# Main.net
KiCad netlist of a schematic drawn in Altium Designer
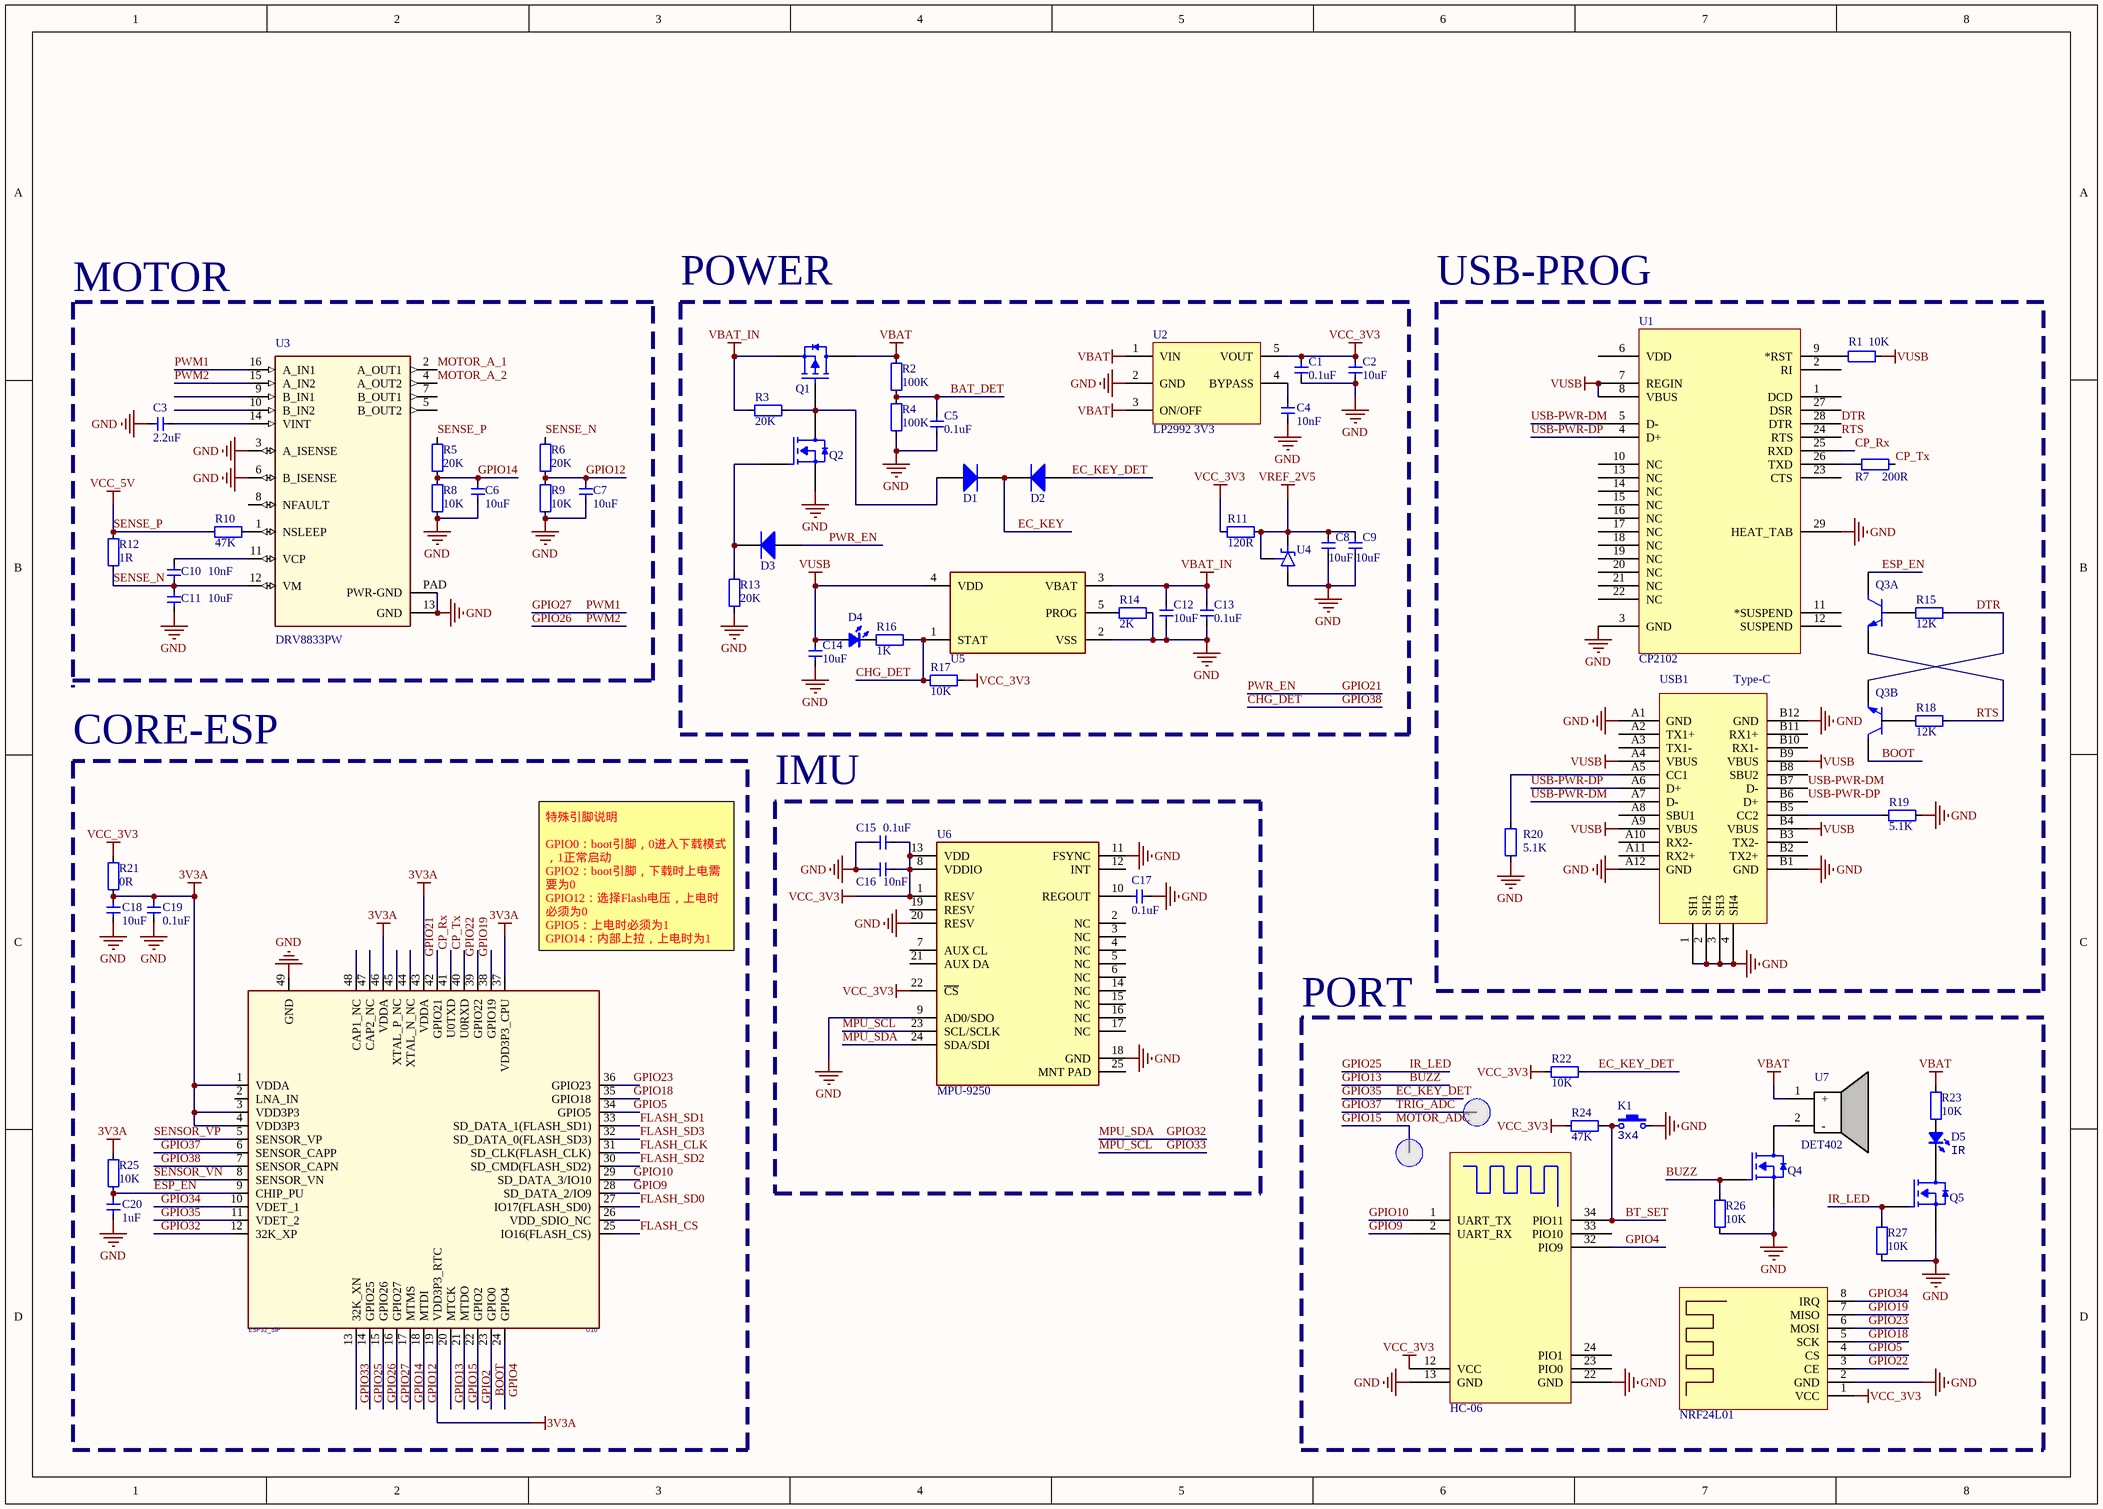
[diagram p0: Main.SchDoc]

(export (version "E")
  (design (tool "Eeschema 10.0.6"))
  (components
    (comp (ref "C1")
      (value "0.1uF")
      (footprint "CAP_0402")
      (description "Capacitor")
      (libsource (lib "MyPcbLib") (part "电容-0402"))
    )
    (comp (ref "C2")
      (value "10uF")
      (footprint "CAP_0402")
      (description "Capacitor")
      (libsource (lib "MyPcbLib") (part "电容-0402"))
    )
    (comp (ref "C3")
      (value "2.2uF")
      (footprint "CAP_0402")
      (description "Capacitor")
      (libsource (lib "MyPcbLib") (part "电容-0402"))
    )
    (comp (ref "C4")
      (value "10nF")
      (footprint "CAP_0402")
      (description "Capacitor")
      (libsource (lib "MyPcbLib") (part "电容-0402"))
    )
    (comp (ref "C5")
      (value "0.1uF")
      (footprint "CAP_0402")
      (description "Capacitor")
      (libsource (lib "MyPcbLib") (part "电容-0402"))
    )
    (comp (ref "C6")
      (value "10uF")
      (footprint "CAP_0402")
      (description "Capacitor")
      (libsource (lib "MyPcbLib") (part "电容-0402"))
    )
    (comp (ref "C7")
      (value "10uF")
      (footprint "CAP_0402")
      (description "Capacitor")
      (libsource (lib "MyPcbLib") (part "电容-0402"))
    )
    (comp (ref "C8")
      (value "10uF")
      (footprint "CAP_0402")
      (description "Capacitor")
      (libsource (lib "MyPcbLib") (part "电容-0402"))
    )
    (comp (ref "C9")
      (value "10uF")
      (footprint "CAP_0402")
      (description "Capacitor")
      (libsource (lib "MyPcbLib") (part "电容-0402"))
    )
    (comp (ref "C10")
      (value "10nF")
      (footprint "CAP_0402")
      (description "Capacitor")
      (libsource (lib "MyPcbLib") (part "电容-0402"))
    )
    (comp (ref "C11")
      (value "10uF")
      (footprint "CAP_0402")
      (description "Capacitor")
      (libsource (lib "MyPcbLib") (part "电容-0402"))
    )
    (comp (ref "C12")
      (value "10uF")
      (footprint "CAP_0402")
      (description "Capacitor")
      (libsource (lib "MyPcbLib") (part "电容-0402"))
    )
    (comp (ref "C13")
      (value "0.1uF")
      (footprint "CAP_0402")
      (description "Capacitor")
      (libsource (lib "MyPcbLib") (part "电容-0402"))
    )
    (comp (ref "C14")
      (value "10uF")
      (footprint "CAP_0402")
      (description "Capacitor")
      (libsource (lib "MyPcbLib") (part "电容-0402"))
    )
    (comp (ref "C15")
      (value "0.1uF")
      (footprint "CAP_0402")
      (description "Capacitor")
      (libsource (lib "MyPcbLib") (part "电容-0402"))
    )
    (comp (ref "C16")
      (value "10nF")
      (footprint "CAP_0402")
      (description "Capacitor")
      (libsource (lib "MyPcbLib") (part "电容-0402"))
    )
    (comp (ref "C17")
      (value "0.1uF")
      (footprint "CAP_0402")
      (description "Capacitor")
      (libsource (lib "MyPcbLib") (part "电容-0402"))
    )
    (comp (ref "C18")
      (value "10uF")
      (footprint "CAP_0402")
      (description "Capacitor")
      (libsource (lib "MyPcbLib") (part "电容-0402"))
    )
    (comp (ref "C19")
      (value "0.1uF")
      (footprint "CAP_0402")
      (description "Capacitor")
      (libsource (lib "MyPcbLib") (part "电容-0402"))
    )
    (comp (ref "C20")
      (value "1uF")
      (footprint "CAP_0402")
      (description "Capacitor")
      (libsource (lib "MyPcbLib") (part "电容-0402"))
    )
    (comp (ref "D1")
      (value "二极管-5819W")
      (footprint "SOD-323")
      (description "40V")
      (libsource (lib "MyPcbLib") (part "二极管-5819W"))
    )
    (comp (ref "D2")
      (value "二极管-5819W")
      (footprint "SOD-323")
      (description "40V")
      (libsource (lib "MyPcbLib") (part "二极管-5819W"))
    )
    (comp (ref "D3")
      (value "二极管-5819W")
      (footprint "SOD-323")
      (description "40V")
      (libsource (lib "MyPcbLib") (part "二极管-5819W"))
    )
    (comp (ref "D4")
      (value "color?")
      (footprint "LED_0402_RED")
      (description "LED")
      (libsource (lib "KitSprout") (part "LED_0402"))
    )
    (comp (ref "D5")
      (value "color?")
      (footprint "LED_0805_RED")
      (description "LED")
      (fields (field (name "TYPE") "IR"))
      (libsource (lib "KitSprout") (part "LED_0805"))
    )
    (comp (ref "K1")
      (value "3x4")
      (footprint "ButtonTACT_3x4x2_180")
      (description "Button")
      (fields (field (name "Comment") "TACT 2P"))
      (libsource (lib "KitSprout") (part "ButtonTACT_3x4x2_180"))
    )
    (comp (ref "Q1")
      (value "AO3401A")
      (footprint "SOT23-3")
      (description "P-MOS")
      (libsource (lib "MyPcbLib") (part "AO3401A"))
    )
    (comp (ref "Q2")
      (value "AO3400A")
      (footprint "SOT23-3")
      (description "N-MOS")
      (libsource (lib "MyPcbLib") (part "AO3400A"))
    )
    (comp (ref "Q3")
      (value "BC847BVC-7")
      (footprint "SOT563-6")
      (libsource (lib "MyPcbLib") (part "BC847BVC-7"))
    )
    (comp (ref "Q4")
      (value "AO3400A")
      (footprint "SOT23-3")
      (description "N-MOS")
      (libsource (lib "MyPcbLib") (part "AO3400A"))
    )
    (comp (ref "Q5")
      (value "AO3400A")
      (footprint "SOT23-3")
      (description "N-MOS")
      (libsource (lib "MyPcbLib") (part "AO3400A"))
    )
    (comp (ref "R1")
      (value "10K")
      (footprint "RES_0402")
      (description "Resistor")
      (libsource (lib "") (part "电阻-0402_2"))
    )
    (comp (ref "R2")
      (value "100K")
      (footprint "RES_0402")
      (description "Resistor")
      (libsource (lib "MyPcbLib") (part "电阻-0402"))
    )
    (comp (ref "R3")
      (value "20K")
      (footprint "RES_0402")
      (description "Resistor")
      (libsource (lib "") (part "电阻-0402_1"))
    )
    (comp (ref "R4")
      (value "100K")
      (footprint "RES_0402")
      (description "Resistor")
      (libsource (lib "MyPcbLib") (part "电阻-0402"))
    )
    (comp (ref "R5")
      (value "20K")
      (footprint "RES_0402")
      (description "Resistor")
      (libsource (lib "MyPcbLib") (part "电阻-0402"))
    )
    (comp (ref "R6")
      (value "20K")
      (footprint "RES_0402")
      (description "Resistor")
      (libsource (lib "MyPcbLib") (part "电阻-0402"))
    )
    (comp (ref "R7")
      (value "200R")
      (footprint "RES_0402")
      (description "Resistor")
      (libsource (lib "") (part "电阻-0402_2"))
    )
    (comp (ref "R8")
      (value "10K")
      (footprint "RES_0402")
      (description "Resistor")
      (libsource (lib "MyPcbLib") (part "电阻-0402"))
    )
    (comp (ref "R9")
      (value "10K")
      (footprint "RES_0402")
      (description "Resistor")
      (libsource (lib "MyPcbLib") (part "电阻-0402"))
    )
    (comp (ref "R10")
      (value "47K")
      (footprint "RES_0402")
      (description "Resistor")
      (libsource (lib "") (part "电阻-0402_2"))
    )
    (comp (ref "R11")
      (value "120R")
      (footprint "RES_0402")
      (description "Resistor")
      (libsource (lib "") (part "电阻-0402_1"))
    )
    (comp (ref "R12")
      (value "1R")
      (footprint "1206-RES")
      (description "Resistor")
      (libsource (lib "MyPcbLib") (part "电阻-1206"))
    )
    (comp (ref "R13")
      (value "20K")
      (footprint "RES_0402")
      (description "Resistor")
      (libsource (lib "MyPcbLib") (part "电阻-0402"))
    )
    (comp (ref "R14")
      (value "2K")
      (footprint "RES_0402")
      (description "Resistor")
      (libsource (lib "") (part "电阻-0402_1"))
    )
    (comp (ref "R15")
      (value "12K")
      (footprint "RES_0402")
      (description "Resistor")
      (libsource (lib "") (part "电阻-0402_2"))
    )
    (comp (ref "R16")
      (value "1K")
      (footprint "RES_0402")
      (description "Resistor")
      (libsource (lib "") (part "电阻-0402_1"))
    )
    (comp (ref "R17")
      (value "10K")
      (footprint "RES_0402")
      (description "Resistor")
      (libsource (lib "") (part "电阻-0402_1"))
    )
    (comp (ref "R18")
      (value "12K")
      (footprint "RES_0402")
      (description "Resistor")
      (libsource (lib "") (part "电阻-0402_2"))
    )
    (comp (ref "R19")
      (value "5.1K")
      (footprint "RES_0402")
      (description "Resistor")
      (libsource (lib "") (part "电阻-0402_2"))
    )
    (comp (ref "R20")
      (value "5.1K")
      (footprint "RES_0402")
      (description "Resistor")
      (libsource (lib "") (part "电阻-0402_3"))
    )
    (comp (ref "R21")
      (value "0R")
      (footprint "RES_0402")
      (description "Resistor")
      (libsource (lib "") (part "电阻-0402_3"))
    )
    (comp (ref "R22")
      (value "10K")
      (footprint "RES_0402")
      (description "Resistor")
      (libsource (lib "") (part "电阻-0402_1"))
    )
    (comp (ref "R23")
      (value "10K")
      (footprint "RES_0402")
      (description "Resistor")
      (libsource (lib "MyPcbLib") (part "电阻-0402"))
    )
    (comp (ref "R24")
      (value "47K")
      (footprint "RES_0402")
      (description "Resistor")
      (libsource (lib "") (part "电阻-0402_1"))
    )
    (comp (ref "R25")
      (value "10K")
      (footprint "RES_0402")
      (description "Resistor")
      (libsource (lib "") (part "电阻-0402_3"))
    )
    (comp (ref "R26")
      (value "10K")
      (footprint "RES_0402")
      (description "Resistor")
      (libsource (lib "MyPcbLib") (part "电阻-0402"))
    )
    (comp (ref "R27")
      (value "10K")
      (footprint "RES_0402")
      (description "Resistor")
      (libsource (lib "MyPcbLib") (part "电阻-0402"))
    )
    (comp (ref "T1") (value "测试点") (footprint "TEST_PT") (libsource (lib "MyPcbLib") (part "测试点")))
    (comp (ref "T2") (value "测试点") (footprint "TEST_PT") (libsource (lib "MyPcbLib") (part "测试点")))
    (comp (ref "U1")
      (value "CP2102")
      (footprint "QFN-28")
      (description "USB转TTL")
      (libsource (lib "mLib") (part "CP2102"))
    )
    (comp (ref "U2")
      (value "LP2992 3V3")
      (footprint "SOT23-5")
      (description "LDO")
      (libsource (lib "mLib") (part "LP2992"))
    )
    (comp (ref "U3") (value "DRV8833PW") (footprint "TSSOP-16") (libsource (lib "mLib") (part "DRV8833PW")))
    (comp (ref "U4")
      (value "TL431IDBZT")
      (footprint "SOT23-3")
      (description "Adjustable precision shunt regulator 3-SOT-23 -40 to 85")
      (fields (field (name "MF") "Texas Instruments"))
      (libsource (lib "MyPcbLib") (part "TL431IDBZT"))
    )
    (comp (ref "U5")
      (value "MCP73831T")
      (footprint "SOT23-5")
      (libsource (lib "MyPcbLib") (part "MCP73831T"))
    )
    (comp (ref "U6")
      (value "MPU9250")
      (footprint "QFN-24-3x3")
      (description "IC IMU ACCEL/GYRO/MAG I2C/SPI 24QFN")
      (fields
        (field (name "MANUFACTURER") "TDK InvenSense")
        (field (name "MOUSER PART NUMBER") "410-MPU-9250")
        (field (name "PART NUMBER") "MPU-9250")
      )
      (libsource (lib "MyPcbLib") (part "MPU9250"))
    )
    (comp (ref "U7") (value "DET402") (footprint "DET402") (libsource (lib "MyPcbLib") (part "DET402")))
    (comp (ref "U8") (value "HC-06") (footprint "蓝牙模块HC-06") (libsource (lib "MyPcbLib") (part "蓝牙模块HC-06")))
    (comp (ref "U9")
      (value "NRF24L01")
      (footprint "NRF24L01-MODULE")
      (libsource (lib "MyPcbLib") (part "NRF24L01模块"))
    )
    (comp (ref "U10")
      (value "ESP32_SIP")
      (footprint "QFN-48_7X7")
      (libsource (lib "mLib") (part "ESP32-PICO"))
    )
    (comp (ref "USB1")
      (value "Type-C")
      (footprint "Type-C-TOP")
      (libsource (lib "MyPcbLib") (part "USB-Type-C-TOP"))
    )
  )
  (nets
    (net (code "1") (name "/BAT_DET") (class "Default")
      (node (ref "C5") (pin "2") (pinfunction "2_2") (pintype "passive"))
      (node (ref "R2") (pin "1") (pinfunction "1_1") (pintype "passive"))
      (node (ref "R4") (pin "2") (pinfunction "2_2") (pintype "passive"))
    )
    (net (code "2") (name "/BOOT") (class "Default")
      (node (ref "Q3") (pin "3") (pinfunction "C2_3") (pintype "passive"))
      (node (ref "U10") (pin "23") (pinfunction "GPIO0_23") (pintype "passive"))
    )
    (net (code "3") (name "/BT_SET") (class "Default")
      (node (ref "K1") (pin "1") (pinfunction "1_1") (pintype "passive"))
      (node (ref "R24") (pin "2") (pinfunction "2_2") (pintype "passive"))
      (node (ref "U8") (pin "34") (pinfunction "PIO11_34") (pintype "passive"))
    )
    (net (code "4") (name "/BUZZ") (class "Default")
      (node (ref "Q4") (pin "1") (pinfunction "G_1") (pintype "passive"))
      (node (ref "R26") (pin "2") (pinfunction "2_2") (pintype "passive"))
      (node (ref "U10") (pin "20") (pinfunction "MTCK_20") (pintype "passive"))
    )
    (net (code "5") (name "/CHG_DET") (class "Default")
      (node (ref "R16") (pin "2") (pinfunction "2_2") (pintype "passive"))
      (node (ref "R17") (pin "1") (pinfunction "1_1") (pintype "passive"))
      (node (ref "U10") (pin "7") (pinfunction "SENSOR_CAPN_7") (pintype "passive"))
      (node (ref "U5") (pin "1") (pinfunction "STAT_1") (pintype "passive"))
    )
    (net (code "6") (name "/CP_Rx") (class "Default")
      (node (ref "U1") (pin "25") (pinfunction "RXD_25") (pintype "passive"))
      (node (ref "U10") (pin "41") (pinfunction "U0TXD_41") (pintype "power_in"))
    )
    (net (code "7") (name "/CP_Tx") (class "Default")
      (node (ref "R7") (pin "1") (pinfunction "1_1") (pintype "passive"))
      (node (ref "U10") (pin "40") (pinfunction "U0RXD_40") (pintype "power_in"))
    )
    (net (code "8") (name "/DTR") (class "Default")
      (node (ref "Q3") (pin "4") (pinfunction "E2_4") (pintype "passive"))
      (node (ref "R15") (pin "1") (pinfunction "1_1") (pintype "passive"))
      (node (ref "U1") (pin "28") (pinfunction "DTR_28") (pintype "passive"))
    )
    (net (code "9") (name "/EC_KEY") (class "Default")
      (node (ref "D1") (pin "2") (pinfunction "K_2") (pintype "passive"))
      (node (ref "D2") (pin "2") (pinfunction "K_2") (pintype "passive"))
    )
    (net (code "10") (name "/EC_KEY_DET") (class "Default")
      (node (ref "D2") (pin "1") (pinfunction "A_1") (pintype "passive"))
      (node (ref "R22") (pin "2") (pinfunction "2_2") (pintype "passive"))
      (node (ref "U10") (pin "11") (pinfunction "VDET_2_11") (pintype "passive"))
    )
    (net (code "11") (name "/ESP_EN") (class "Default")
      (node (ref "C20") (pin "1") (pinfunction "1_1") (pintype "passive"))
      (node (ref "Q3") (pin "6") (pinfunction "C1_6") (pintype "passive"))
      (node (ref "R25") (pin "2") (pinfunction "2_2") (pintype "passive"))
      (node (ref "U10") (pin "9") (pinfunction "CHIP_PU_9") (pintype "passive"))
    )
    (net (code "12") (name "/FLASH_CLK") (class "Default")
      (node (ref "U10") (pin "31") (pinfunction "SD_CLK(FLASH_CLK)_31") (pintype "passive"))
    )
    (net (code "13") (name "/FLASH_CS") (class "Default")
      (node (ref "U10") (pin "25") (pinfunction "IO16(FLASH_CS)_25") (pintype "passive"))
    )
    (net (code "14") (name "/FLASH_SD0") (class "Default")
      (node (ref "U10") (pin "27") (pinfunction "IO17(FLASH_SD0)_27") (pintype "passive"))
    )
    (net (code "15") (name "/FLASH_SD1") (class "Default")
      (node (ref "U10") (pin "33") (pinfunction "SD_DATA_1(FLASH_SD1)_33") (pintype "passive"))
    )
    (net (code "16") (name "/FLASH_SD2") (class "Default")
      (node (ref "U10") (pin "30") (pinfunction "SD_CMD(FLASH_SD2)_30") (pintype "passive"))
    )
    (net (code "17") (name "/FLASH_SD3") (class "Default")
      (node (ref "U10") (pin "32") (pinfunction "SD_DATA_0(FLASH_SD3)_32") (pintype "passive"))
    )
    (net (code "18") (name "/GPIO2") (class "Default")
      (node (ref "U10") (pin "22") (pinfunction "GPIO2_22") (pintype "passive"))
    )
    (net (code "19") (name "/GPIO4") (class "Default")
      (node (ref "U10") (pin "24") (pinfunction "GPIO4_24") (pintype "passive"))
      (node (ref "U8") (pin "32") (pinfunction "PIO9_32") (pintype "passive"))
    )
    (net (code "20") (name "/GPIO5") (class "Default")
      (node (ref "U10") (pin "34") (pinfunction "GPIO5_34") (pintype "passive"))
      (node (ref "U9") (pin "4") (pinfunction "CS_4") (pintype "passive"))
    )
    (net (code "21") (name "/GPIO9") (class "Default")
      (node (ref "U10") (pin "28") (pinfunction "SD_DATA_2/IO9_28") (pintype "passive"))
      (node (ref "U8") (pin "2") (pinfunction "UART_RX_2") (pintype "passive"))
    )
    (net (code "22") (name "/GPIO10") (class "Default")
      (node (ref "U10") (pin "29") (pinfunction "SD_DATA_3/IO10_29") (pintype "passive"))
      (node (ref "U8") (pin "1") (pinfunction "UART_TX_1") (pintype "passive"))
    )
    (net (code "23") (name "/GPIO12") (class "Default")
      (node (ref "C7") (pin "2") (pinfunction "2_2") (pintype "passive"))
      (node (ref "R6") (pin "1") (pinfunction "1_1") (pintype "passive"))
      (node (ref "R9") (pin "2") (pinfunction "2_2") (pintype "passive"))
      (node (ref "U10") (pin "18") (pinfunction "MTDI_18") (pintype "passive"))
    )
    (net (code "24") (name "/GPIO14") (class "Default")
      (node (ref "C6") (pin "2") (pinfunction "2_2") (pintype "passive"))
      (node (ref "R5") (pin "1") (pinfunction "1_1") (pintype "passive"))
      (node (ref "R8") (pin "2") (pinfunction "2_2") (pintype "passive"))
      (node (ref "U10") (pin "17") (pinfunction "MTMS_17") (pintype "passive"))
    )
    (net (code "25") (name "/GPIO15") (class "Default")
      (node (ref "T2") (pin "0") (pinfunction "0_0") (pintype "passive"))
      (node (ref "U10") (pin "21") (pinfunction "MTDO_21") (pintype "passive"))
    )
    (net (code "26") (name "/GPIO18") (class "Default")
      (node (ref "U10") (pin "35") (pinfunction "GPIO18_35") (pintype "passive"))
      (node (ref "U9") (pin "5") (pinfunction "SCK_5") (pintype "passive"))
    )
    (net (code "27") (name "/GPIO19") (class "Default")
      (node (ref "U10") (pin "38") (pinfunction "GPIO19_38") (pintype "passive"))
      (node (ref "U9") (pin "7") (pinfunction "MISO_7") (pintype "passive"))
    )
    (net (code "28") (name "/GPIO21") (class "Default")
      (node (ref "D3") (pin "1") (pinfunction "A_1") (pintype "passive"))
      (node (ref "U10") (pin "42") (pinfunction "GPIO21_42") (pintype "passive"))
    )
    (net (code "29") (name "/GPIO22") (class "Default")
      (node (ref "U10") (pin "39") (pinfunction "GPIO22_39") (pintype "passive"))
      (node (ref "U9") (pin "3") (pinfunction "CE_3") (pintype "passive"))
    )
    (net (code "30") (name "/GPIO23") (class "Default")
      (node (ref "U10") (pin "36") (pinfunction "GPIO23_36") (pintype "passive"))
      (node (ref "U9") (pin "6") (pinfunction "MOSI_6") (pintype "passive"))
    )
    (net (code "31") (name "/GPIO25") (class "Default")
      (node (ref "Q5") (pin "1") (pinfunction "G_1") (pintype "passive"))
      (node (ref "R27") (pin "2") (pinfunction "2_2") (pintype "passive"))
      (node (ref "U10") (pin "14") (pinfunction "GPIO25_14") (pintype "passive"))
    )
    (net (code "32") (name "/GPIO26") (class "Default")
      (node (ref "U10") (pin "15") (pinfunction "GPIO26_15") (pintype "passive"))
      (node (ref "U3") (pin "15") (pinfunction "A_IN2_15") (pintype "input"))
    )
    (net (code "33") (name "/GPIO27") (class "Default")
      (node (ref "U10") (pin "16") (pinfunction "GPIO27_16") (pintype "passive"))
      (node (ref "U3") (pin "16") (pinfunction "A_IN1_16") (pintype "input"))
    )
    (net (code "34") (name "/GPIO32") (class "Default")
      (node (ref "U10") (pin "12") (pinfunction "32K_XP_12") (pintype "passive"))
      (node (ref "U6") (pin "24") (pinfunction "SDA/SDI_24") (pintype "passive"))
    )
    (net (code "35") (name "/GPIO33") (class "Default")
      (node (ref "U10") (pin "13") (pinfunction "32K_XN_13") (pintype "passive"))
      (node (ref "U6") (pin "23") (pinfunction "SCL/SCLK_23") (pintype "passive"))
    )
    (net (code "36") (name "/GPIO34") (class "Default")
      (node (ref "U10") (pin "10") (pinfunction "VDET_1_10") (pintype "passive"))
      (node (ref "U9") (pin "8") (pinfunction "IRQ_8") (pintype "passive"))
    )
    (net (code "37") (name "/GPIO37") (class "Default")
      (node (ref "T1") (pin "0") (pinfunction "0_0") (pintype "passive"))
      (node (ref "U10") (pin "6") (pinfunction "SENSOR_CAPP_6") (pintype "passive"))
    )
    (net (code "38") (name "/MOTOR_A_1") (class "Default")
      (node (ref "U3") (pin "2") (pinfunction "A_OUT1_2") (pintype "output"))
    )
    (net (code "39") (name "/MOTOR_A_2") (class "Default")
      (node (ref "U3") (pin "4") (pinfunction "A_OUT2_4") (pintype "output"))
    )
    (net (code "40") (name "/RTS") (class "Default")
      (node (ref "Q3") (pin "1") (pinfunction "E1_1") (pintype "passive"))
      (node (ref "R18") (pin "1") (pinfunction "1_1") (pintype "passive"))
      (node (ref "U1") (pin "24") (pinfunction "RTS_24") (pintype "passive"))
    )
    (net (code "41") (name "/SENSE_N") (class "Default")
      (node (ref "C10") (pin "1") (pinfunction "1_1") (pintype "passive"))
      (node (ref "C11") (pin "2") (pinfunction "2_2") (pintype "passive"))
      (node (ref "R12") (pin "1") (pinfunction "1_1") (pintype "passive"))
      (node (ref "R6") (pin "2") (pinfunction "2_2") (pintype "passive"))
      (node (ref "U3") (pin "12") (pinfunction "VM_12") (pintype "bidirectional"))
    )
    (net (code "42") (name "/SENSOR_VN") (class "Default")
      (node (ref "U10") (pin "8") (pinfunction "SENSOR_VN_8") (pintype "passive"))
    )
    (net (code "43") (name "/SENSOR_VP") (class "Default")
      (node (ref "U10") (pin "5") (pinfunction "SENSOR_VP_5") (pintype "passive"))
    )
    (net (code "44") (name "/USB-PWR-DM") (class "Default")
      (node (ref "U1") (pin "5") (pinfunction "D-_5") (pintype "passive"))
      (node (ref "USB1") (pin "A7") (pinfunction "D-_A7") (pintype "passive"))
      (node (ref "USB1") (pin "B7") (pinfunction "D-_B7") (pintype "passive"))
    )
    (net (code "45") (name "/USB-PWR-DP") (class "Default")
      (node (ref "U1") (pin "4") (pinfunction "D+_4") (pintype "passive"))
      (node (ref "USB1") (pin "A6") (pinfunction "D+_A6") (pintype "passive"))
      (node (ref "USB1") (pin "B6") (pinfunction "D+_B6") (pintype "passive"))
    )
    (net (code "46") (name "3V3A") (class "Default")
      (node (ref "C18") (pin "2") (pinfunction "2_2") (pintype "passive"))
      (node (ref "C19") (pin "2") (pinfunction "2_2") (pintype "passive"))
      (node (ref "R21") (pin "2") (pinfunction "2_2") (pintype "passive"))
      (node (ref "R25") (pin "1") (pinfunction "1_1") (pintype "passive"))
      (node (ref "U10") (pin "1") (pinfunction "VDDA_1") (pintype "power_in"))
      (node (ref "U10") (pin "19") (pinfunction "VDD3P3_RTC_19") (pintype "power_in"))
      (node (ref "U10") (pin "3") (pinfunction "VDD3P3_3") (pintype "power_in"))
      (node (ref "U10") (pin "37") (pinfunction "VDD3P3_CPU_37") (pintype "power_in"))
      (node (ref "U10") (pin "4") (pinfunction "VDD3P3_4") (pintype "power_in"))
      (node (ref "U10") (pin "43") (pinfunction "VDDA_43") (pintype "power_in"))
      (node (ref "U10") (pin "46") (pinfunction "VDDA_46") (pintype "power_in"))
    )
    (net (code "47") (name "GND") (class "Default")
      (node (ref "C1") (pin "1") (pinfunction "1_1") (pintype "passive"))
      (node (ref "C11") (pin "1") (pinfunction "1_1") (pintype "passive"))
      (node (ref "C12") (pin "1") (pinfunction "1_1") (pintype "passive"))
      (node (ref "C13") (pin "1") (pinfunction "1_1") (pintype "passive"))
      (node (ref "C14") (pin "1") (pinfunction "1_1") (pintype "passive"))
      (node (ref "C15") (pin "2") (pinfunction "2_2") (pintype "passive"))
      (node (ref "C16") (pin "2") (pinfunction "2_2") (pintype "passive"))
      (node (ref "C17") (pin "1") (pinfunction "1_1") (pintype "passive"))
      (node (ref "C18") (pin "1") (pinfunction "1_1") (pintype "passive"))
      (node (ref "C19") (pin "1") (pinfunction "1_1") (pintype "passive"))
      (node (ref "C2") (pin "1") (pinfunction "1_1") (pintype "passive"))
      (node (ref "C20") (pin "2") (pinfunction "2_2") (pintype "passive"))
      (node (ref "C3") (pin "1") (pinfunction "1_1") (pintype "passive"))
      (node (ref "C4") (pin "1") (pinfunction "1_1") (pintype "passive"))
      (node (ref "C5") (pin "1") (pinfunction "1_1") (pintype "passive"))
      (node (ref "C6") (pin "1") (pinfunction "1_1") (pintype "passive"))
      (node (ref "C7") (pin "1") (pinfunction "1_1") (pintype "passive"))
      (node (ref "C8") (pin "1") (pinfunction "1_1") (pintype "passive"))
      (node (ref "C9") (pin "1") (pinfunction "1_1") (pintype "passive"))
      (node (ref "K1") (pin "2") (pinfunction "2_2") (pintype "passive"))
      (node (ref "Q2") (pin "2") (pinfunction "S_2") (pintype "passive"))
      (node (ref "Q4") (pin "2") (pinfunction "S_2") (pintype "passive"))
      (node (ref "Q5") (pin "2") (pinfunction "S_2") (pintype "passive"))
      (node (ref "R13") (pin "1") (pinfunction "1_1") (pintype "passive"))
      (node (ref "R14") (pin "2") (pinfunction "2_2") (pintype "passive"))
      (node (ref "R19") (pin "1") (pinfunction "1_1") (pintype "passive"))
      (node (ref "R20") (pin "2") (pinfunction "2_2") (pintype "passive"))
      (node (ref "R26") (pin "1") (pinfunction "1_1") (pintype "passive"))
      (node (ref "R27") (pin "1") (pinfunction "1_1") (pintype "passive"))
      (node (ref "R4") (pin "1") (pinfunction "1_1") (pintype "passive"))
      (node (ref "R8") (pin "1") (pinfunction "1_1") (pintype "passive"))
      (node (ref "R9") (pin "1") (pinfunction "1_1") (pintype "passive"))
      (node (ref "U1") (pin "29") (pinfunction "HEAT_TAB_29") (pintype "passive"))
      (node (ref "U1") (pin "3") (pinfunction "GND_3") (pintype "passive"))
      (node (ref "U10") (pin "49") (pinfunction "GND_49") (pintype "power_in"))
      (node (ref "U2") (pin "2") (pinfunction "GND_2") (pintype "passive"))
      (node (ref "U3") (pin "13") (pinfunction "GND_13") (pintype "power_in"))
      (node (ref "U3") (pin "3") (pinfunction "A_ISENSE_3") (pintype "bidirectional"))
      (node (ref "U3") (pin "6") (pinfunction "B_ISENSE_6") (pintype "bidirectional"))
      (node (ref "U3") (pin "PAD") (pinfunction "PWR-GND_PAD") (pintype "power_in"))
      (node (ref "U4") (pin "3") (pinfunction "ANODE_3") (pintype "passive"))
      (node (ref "U5") (pin "2") (pinfunction "VSS_2") (pintype "power_in"))
      (node (ref "U6") (pin "11") (pinfunction "FSYNC_11") (pintype "passive"))
      (node (ref "U6") (pin "18") (pinfunction "GND_18") (pintype "passive"))
      (node (ref "U6") (pin "20") (pinfunction "RESV_20") (pintype "passive"))
      (node (ref "U6") (pin "9") (pinfunction "AD0/SDO_9") (pintype "passive"))
      (node (ref "U8") (pin "13") (pinfunction "GND_13") (pintype "passive"))
      (node (ref "U8") (pin "22") (pinfunction "GND_22") (pintype "passive"))
      (node (ref "U9") (pin "2") (pinfunction "GND_2") (pintype "passive"))
      (node (ref "USB1") (pin "1") (pinfunction "SH1_1") (pintype "passive"))
      (node (ref "USB1") (pin "2") (pinfunction "SH2_2") (pintype "passive"))
      (node (ref "USB1") (pin "3") (pinfunction "SH3_3") (pintype "passive"))
      (node (ref "USB1") (pin "4") (pinfunction "SH4_4") (pintype "passive"))
      (node (ref "USB1") (pin "A1") (pinfunction "GND_A1") (pintype "passive"))
      (node (ref "USB1") (pin "A12") (pinfunction "GND_A12") (pintype "passive"))
      (node (ref "USB1") (pin "B1") (pinfunction "GND_B1") (pintype "passive"))
      (node (ref "USB1") (pin "B12") (pinfunction "GND_B12") (pintype "passive"))
    )
    (net (code "48") (name "Net-(D1-A)") (class "Default")
      (node (ref "D1") (pin "1") (pinfunction "A_1") (pintype "passive"))
      (node (ref "Q1") (pin "1") (pinfunction "G_1") (pintype "passive"))
      (node (ref "Q2") (pin "3") (pinfunction "D_3") (pintype "passive"))
      (node (ref "R3") (pin "2") (pinfunction "2_2") (pintype "passive"))
    )
    (net (code "49") (name "Net-(D3-K)") (class "Default")
      (node (ref "D3") (pin "2") (pinfunction "K_2") (pintype "passive"))
      (node (ref "Q2") (pin "1") (pinfunction "G_1") (pintype "passive"))
      (node (ref "R13") (pin "2") (pinfunction "2_2") (pintype "passive"))
    )
    (net (code "50") (name "Net-(D4-K)") (class "Default")
      (node (ref "D4") (pin "2") (pinfunction "K_2") (pintype "passive"))
      (node (ref "R16") (pin "1") (pinfunction "1_1") (pintype "passive"))
    )
    (net (code "51") (name "Net-(D5-A)") (class "Default")
      (node (ref "D5") (pin "1") (pinfunction "A_1") (pintype "passive"))
      (node (ref "R23") (pin "1") (pinfunction "1_1") (pintype "passive"))
    )
    (net (code "52") (name "Net-(D5-K)") (class "Default")
      (node (ref "D5") (pin "2") (pinfunction "K_2") (pintype "passive"))
      (node (ref "Q5") (pin "3") (pinfunction "D_3") (pintype "passive"))
    )
    (net (code "53") (name "Net-(Q3A-B1)") (class "Default")
      (node (ref "Q3") (pin "2") (pinfunction "B1_2") (pintype "passive"))
      (node (ref "R15") (pin "2") (pinfunction "2_2") (pintype "passive"))
    )
    (net (code "54") (name "Net-(Q3B-B2)") (class "Default")
      (node (ref "Q3") (pin "5") (pinfunction "B2_5") (pintype "passive"))
      (node (ref "R18") (pin "2") (pinfunction "2_2") (pintype "passive"))
    )
    (net (code "55") (name "Net-(Q4-D)") (class "Default")
      (node (ref "Q4") (pin "3") (pinfunction "D_3") (pintype "passive"))
      (node (ref "U7") (pin "2") (pinfunction "-_2") (pintype "passive"))
    )
    (net (code "56") (name "Net-(U1-*RST)") (class "Default")
      (node (ref "R1") (pin "2") (pinfunction "2_2") (pintype "passive"))
      (node (ref "U1") (pin "9") (pinfunction "*RST_9") (pintype "passive"))
    )
    (net (code "57") (name "Net-(U1-TXD)") (class "Default")
      (node (ref "R7") (pin "2") (pinfunction "2_2") (pintype "passive"))
      (node (ref "U1") (pin "26") (pinfunction "TXD_26") (pintype "passive"))
    )
    (net (code "58") (name "Net-(U2-BYPASS)") (class "Default")
      (node (ref "C4") (pin "2") (pinfunction "2_2") (pintype "passive"))
      (node (ref "U2") (pin "4") (pinfunction "BYPASS_4") (pintype "passive"))
    )
    (net (code "59") (name "Net-(U3-NSLEEP)") (class "Default")
      (node (ref "R10") (pin "1") (pinfunction "1_1") (pintype "passive"))
      (node (ref "U3") (pin "1") (pinfunction "NSLEEP_1") (pintype "bidirectional"))
    )
    (net (code "60") (name "Net-(U3-VCP)") (class "Default")
      (node (ref "C10") (pin "2") (pinfunction "2_2") (pintype "passive"))
      (node (ref "U3") (pin "11") (pinfunction "VCP_11") (pintype "bidirectional"))
    )
    (net (code "61") (name "Net-(U3-VINT)") (class "Default")
      (node (ref "C3") (pin "2") (pinfunction "2_2") (pintype "passive"))
      (node (ref "U3") (pin "14") (pinfunction "VINT_14") (pintype "input"))
    )
    (net (code "62") (name "Net-(U5-PROG)") (class "Default")
      (node (ref "R14") (pin "1") (pinfunction "1_1") (pintype "passive"))
      (node (ref "U5") (pin "5") (pinfunction "PROG_5") (pintype "passive"))
    )
    (net (code "63") (name "Net-(U6-REGOUT)") (class "Default")
      (node (ref "C17") (pin "2") (pinfunction "2_2") (pintype "passive"))
      (node (ref "U6") (pin "10") (pinfunction "REGOUT_10") (pintype "passive"))
    )
    (net (code "64") (name "Net-(USB1-CC1)") (class "Default")
      (node (ref "R20") (pin "1") (pinfunction "1_1") (pintype "passive"))
      (node (ref "USB1") (pin "A5") (pinfunction "CC1_A5") (pintype "passive"))
    )
    (net (code "65") (name "Net-(USB1-CC2)") (class "Default")
      (node (ref "R19") (pin "2") (pinfunction "2_2") (pintype "passive"))
      (node (ref "USB1") (pin "B5") (pinfunction "CC2_B5") (pintype "passive"))
    )
    (net (code "66") (name "VBAT") (class "Default")
      (node (ref "Q1") (pin "3") (pinfunction "D_3") (pintype "passive"))
      (node (ref "R2") (pin "2") (pinfunction "2_2") (pintype "passive"))
      (node (ref "R23") (pin "2") (pinfunction "2_2") (pintype "passive"))
      (node (ref "U2") (pin "1") (pinfunction "VIN_1") (pintype "passive"))
      (node (ref "U2") (pin "3") (pinfunction "ON/OFF_3") (pintype "passive"))
      (node (ref "U7") (pin "1") (pinfunction "+_1") (pintype "passive"))
    )
    (net (code "67") (name "VBAT_IN") (class "Default")
      (node (ref "C12") (pin "2") (pinfunction "2_2") (pintype "passive"))
      (node (ref "C13") (pin "2") (pinfunction "2_2") (pintype "passive"))
      (node (ref "Q1") (pin "2") (pinfunction "S_2") (pintype "passive"))
      (node (ref "R3") (pin "1") (pinfunction "1_1") (pintype "passive"))
      (node (ref "U5") (pin "3") (pinfunction "VBAT_3") (pintype "power_in"))
    )
    (net (code "68") (name "VCC_3V3") (class "Default")
      (node (ref "C1") (pin "2") (pinfunction "2_2") (pintype "passive"))
      (node (ref "C15") (pin "1") (pinfunction "1_1") (pintype "passive"))
      (node (ref "C16") (pin "1") (pinfunction "1_1") (pintype "passive"))
      (node (ref "C2") (pin "2") (pinfunction "2_2") (pintype "passive"))
      (node (ref "R11") (pin "1") (pinfunction "1_1") (pintype "passive"))
      (node (ref "R17") (pin "2") (pinfunction "2_2") (pintype "passive"))
      (node (ref "R21") (pin "1") (pinfunction "1_1") (pintype "passive"))
      (node (ref "R22") (pin "1") (pinfunction "1_1") (pintype "passive"))
      (node (ref "R24") (pin "1") (pinfunction "1_1") (pintype "passive"))
      (node (ref "U2") (pin "5") (pinfunction "VOUT_5") (pintype "passive"))
      (node (ref "U6") (pin "1") (pinfunction "RESV_1") (pintype "passive"))
      (node (ref "U6") (pin "13") (pinfunction "VDD_13") (pintype "passive"))
      (node (ref "U6") (pin "22") (pinfunction "~{CS}_22") (pintype "passive"))
      (node (ref "U6") (pin "8") (pinfunction "VDDIO_8") (pintype "passive"))
      (node (ref "U8") (pin "12") (pinfunction "VCC_12") (pintype "passive"))
      (node (ref "U9") (pin "1") (pinfunction "VCC_1") (pintype "passive"))
    )
    (net (code "69") (name "VCC_5V") (class "Default")
      (node (ref "R10") (pin "2") (pinfunction "2_2") (pintype "passive"))
      (node (ref "R12") (pin "2") (pinfunction "2_2") (pintype "passive"))
      (node (ref "R5") (pin "2") (pinfunction "2_2") (pintype "passive"))
    )
    (net (code "70") (name "VREF_2V5") (class "Default")
      (node (ref "C8") (pin "2") (pinfunction "2_2") (pintype "passive"))
      (node (ref "C9") (pin "2") (pinfunction "2_2") (pintype "passive"))
      (node (ref "R11") (pin "2") (pinfunction "2_2") (pintype "passive"))
      (node (ref "U4") (pin "1") (pinfunction "CATHODE_1") (pintype "passive"))
      (node (ref "U4") (pin "2") (pinfunction "REF_2") (pintype "passive"))
    )
    (net (code "71") (name "VUSB") (class "Default")
      (node (ref "C14") (pin "2") (pinfunction "2_2") (pintype "passive"))
      (node (ref "D4") (pin "1") (pinfunction "A_1") (pintype "passive"))
      (node (ref "R1") (pin "1") (pinfunction "1_1") (pintype "passive"))
      (node (ref "U1") (pin "7") (pinfunction "REGIN_7") (pintype "passive"))
      (node (ref "U1") (pin "8") (pinfunction "VBUS_8") (pintype "passive"))
      (node (ref "U5") (pin "4") (pinfunction "VDD_4") (pintype "power_in"))
      (node (ref "USB1") (pin "A4") (pinfunction "VBUS_A4") (pintype "passive"))
      (node (ref "USB1") (pin "A9") (pinfunction "VBUS_A9") (pintype "passive"))
      (node (ref "USB1") (pin "B4") (pinfunction "VBUS_B4") (pintype "passive"))
      (node (ref "USB1") (pin "B9") (pinfunction "VBUS_B9") (pintype "passive"))
    )
    (net (code "72") (name "unconnected-(U1-*SUSPEND-Pad11)") (class "Default")
      (node (ref "U1") (pin "11") (pinfunction "*SUSPEND_11") (pintype "passive"))
    )
    (net (code "73") (name "unconnected-(U1-CTS-Pad23)") (class "Default")
      (node (ref "U1") (pin "23") (pinfunction "CTS_23") (pintype "passive"))
    )
    (net (code "74") (name "unconnected-(U1-DCD-Pad1)") (class "Default")
      (node (ref "U1") (pin "1") (pinfunction "DCD_1") (pintype "passive"))
    )
    (net (code "75") (name "unconnected-(U1-DSR-Pad27)") (class "Default")
      (node (ref "U1") (pin "27") (pinfunction "DSR_27") (pintype "passive"))
    )
    (net (code "76") (name "unconnected-(U1-NC-Pad10)") (class "Default")
      (node (ref "U1") (pin "10") (pinfunction "NC_10") (pintype "passive"))
    )
    (net (code "77") (name "unconnected-(U1-NC-Pad13)") (class "Default")
      (node (ref "U1") (pin "13") (pinfunction "NC_13") (pintype "passive"))
    )
    (net (code "78") (name "unconnected-(U1-NC-Pad14)") (class "Default")
      (node (ref "U1") (pin "14") (pinfunction "NC_14") (pintype "passive"))
    )
    (net (code "79") (name "unconnected-(U1-NC-Pad15)") (class "Default")
      (node (ref "U1") (pin "15") (pinfunction "NC_15") (pintype "passive"))
    )
    (net (code "80") (name "unconnected-(U1-NC-Pad16)") (class "Default")
      (node (ref "U1") (pin "16") (pinfunction "NC_16") (pintype "passive"))
    )
    (net (code "81") (name "unconnected-(U1-NC-Pad17)") (class "Default")
      (node (ref "U1") (pin "17") (pinfunction "NC_17") (pintype "passive"))
    )
    (net (code "82") (name "unconnected-(U1-NC-Pad18)") (class "Default")
      (node (ref "U1") (pin "18") (pinfunction "NC_18") (pintype "passive"))
    )
    (net (code "83") (name "unconnected-(U1-NC-Pad19)") (class "Default")
      (node (ref "U1") (pin "19") (pinfunction "NC_19") (pintype "passive"))
    )
    (net (code "84") (name "unconnected-(U1-NC-Pad20)") (class "Default")
      (node (ref "U1") (pin "20") (pinfunction "NC_20") (pintype "passive"))
    )
    (net (code "85") (name "unconnected-(U1-NC-Pad21)") (class "Default")
      (node (ref "U1") (pin "21") (pinfunction "NC_21") (pintype "passive"))
    )
    (net (code "86") (name "unconnected-(U1-NC-Pad22)") (class "Default")
      (node (ref "U1") (pin "22") (pinfunction "NC_22") (pintype "passive"))
    )
    (net (code "87") (name "unconnected-(U1-RI-Pad2)") (class "Default")
      (node (ref "U1") (pin "2") (pinfunction "RI_2") (pintype "passive"))
    )
    (net (code "88") (name "unconnected-(U1-SUSPEND-Pad12)") (class "Default")
      (node (ref "U1") (pin "12") (pinfunction "SUSPEND_12") (pintype "passive"))
    )
    (net (code "89") (name "unconnected-(U1-VDD-Pad6)") (class "Default")
      (node (ref "U1") (pin "6") (pinfunction "VDD_6") (pintype "passive"))
    )
    (net (code "90") (name "unconnected-(U3-B_IN1-Pad9)") (class "Default")
      (node (ref "U3") (pin "9") (pinfunction "B_IN1_9") (pintype "input"))
    )
    (net (code "91") (name "unconnected-(U3-B_IN2-Pad10)") (class "Default")
      (node (ref "U3") (pin "10") (pinfunction "B_IN2_10") (pintype "input"))
    )
    (net (code "92") (name "unconnected-(U3-B_OUT1-Pad7)") (class "Default")
      (node (ref "U3") (pin "7") (pinfunction "B_OUT1_7") (pintype "output"))
    )
    (net (code "93") (name "unconnected-(U3-B_OUT2-Pad5)") (class "Default")
      (node (ref "U3") (pin "5") (pinfunction "B_OUT2_5") (pintype "output"))
    )
    (net (code "94") (name "unconnected-(U3-NFAULT-Pad8)") (class "Default")
      (node (ref "U3") (pin "8") (pinfunction "NFAULT_8") (pintype "bidirectional"))
    )
    (net (code "95") (name "unconnected-(U6-AUX_CL-Pad7)") (class "Default")
      (node (ref "U6") (pin "7") (pinfunction "AUX_CL_7") (pintype "passive"))
    )
    (net (code "96") (name "unconnected-(U6-AUX_DA-Pad21)") (class "Default")
      (node (ref "U6") (pin "21") (pinfunction "AUX_DA_21") (pintype "passive"))
    )
    (net (code "97") (name "unconnected-(U6-INT-Pad12)") (class "Default")
      (node (ref "U6") (pin "12") (pinfunction "INT_12") (pintype "passive"))
    )
    (net (code "98") (name "unconnected-(U6-MNT_PAD-Pad25)") (class "Default")
      (node (ref "U6") (pin "25") (pinfunction "MNT_PAD_25") (pintype "passive"))
    )
    (net (code "99") (name "unconnected-(U6-NC-Pad2)") (class "Default")
      (node (ref "U6") (pin "2") (pinfunction "NC_2") (pintype "passive"))
    )
    (net (code "100") (name "unconnected-(U6-NC-Pad3)") (class "Default")
      (node (ref "U6") (pin "3") (pinfunction "NC_3") (pintype "passive"))
    )
    (net (code "101") (name "unconnected-(U6-NC-Pad4)") (class "Default")
      (node (ref "U6") (pin "4") (pinfunction "NC_4") (pintype "passive"))
    )
    (net (code "102") (name "unconnected-(U6-NC-Pad5)") (class "Default")
      (node (ref "U6") (pin "5") (pinfunction "NC_5") (pintype "passive"))
    )
    (net (code "103") (name "unconnected-(U6-NC-Pad6)") (class "Default")
      (node (ref "U6") (pin "6") (pinfunction "NC_6") (pintype "passive"))
    )
    (net (code "104") (name "unconnected-(U6-NC-Pad14)") (class "Default")
      (node (ref "U6") (pin "14") (pinfunction "NC_14") (pintype "passive"))
    )
    (net (code "105") (name "unconnected-(U6-NC-Pad15)") (class "Default")
      (node (ref "U6") (pin "15") (pinfunction "NC_15") (pintype "passive"))
    )
    (net (code "106") (name "unconnected-(U6-NC-Pad16)") (class "Default")
      (node (ref "U6") (pin "16") (pinfunction "NC_16") (pintype "passive"))
    )
    (net (code "107") (name "unconnected-(U6-NC-Pad17)") (class "Default")
      (node (ref "U6") (pin "17") (pinfunction "NC_17") (pintype "passive"))
    )
    (net (code "108") (name "unconnected-(U6-RESV-Pad19)") (class "Default")
      (node (ref "U6") (pin "19") (pinfunction "RESV_19") (pintype "passive"))
    )
    (net (code "109") (name "unconnected-(U8-PIO0-Pad23)") (class "Default")
      (node (ref "U8") (pin "23") (pinfunction "PIO0_23") (pintype "passive"))
    )
    (net (code "110") (name "unconnected-(U8-PIO1-Pad24)") (class "Default")
      (node (ref "U8") (pin "24") (pinfunction "PIO1_24") (pintype "passive"))
    )
    (net (code "111") (name "unconnected-(U8-PIO10-Pad33)") (class "Default")
      (node (ref "U8") (pin "33") (pinfunction "PIO10_33") (pintype "passive"))
    )
    (net (code "112") (name "unconnected-(U10-CAP1_NC-Pad48)") (class "Default")
      (node (ref "U10") (pin "48") (pinfunction "CAP1_NC_48") (pintype "passive"))
    )
    (net (code "113") (name "unconnected-(U10-CAP2_NC-Pad47)") (class "Default")
      (node (ref "U10") (pin "47") (pinfunction "CAP2_NC_47") (pintype "passive"))
    )
    (net (code "114") (name "unconnected-(U10-LNA_IN-Pad2)") (class "Default")
      (node (ref "U10") (pin "2") (pinfunction "LNA_IN_2") (pintype "passive"))
    )
    (net (code "115") (name "unconnected-(U10-VDD_SDIO_NC-Pad26)") (class "Default")
      (node (ref "U10") (pin "26") (pinfunction "VDD_SDIO_NC_26") (pintype "passive"))
    )
    (net (code "116") (name "unconnected-(U10-XTAL_N_NC-Pad44)") (class "Default")
      (node (ref "U10") (pin "44") (pinfunction "XTAL_N_NC_44") (pintype "passive"))
    )
    (net (code "117") (name "unconnected-(U10-XTAL_P_NC-Pad45)") (class "Default")
      (node (ref "U10") (pin "45") (pinfunction "XTAL_P_NC_45") (pintype "passive"))
    )
    (net (code "118") (name "unconnected-(USB1-RX1+-PadB11)") (class "Default")
      (node (ref "USB1") (pin "B11") (pinfunction "RX1+_B11") (pintype "passive"))
    )
    (net (code "119") (name "unconnected-(USB1-RX1--PadB10)") (class "Default")
      (node (ref "USB1") (pin "B10") (pinfunction "RX1-_B10") (pintype "passive"))
    )
    (net (code "120") (name "unconnected-(USB1-RX2+-PadA11)") (class "Default")
      (node (ref "USB1") (pin "A11") (pinfunction "RX2+_A11") (pintype "passive"))
    )
    (net (code "121") (name "unconnected-(USB1-RX2--PadA10)") (class "Default")
      (node (ref "USB1") (pin "A10") (pinfunction "RX2-_A10") (pintype "passive"))
    )
    (net (code "122") (name "unconnected-(USB1-SBU1-PadA8)") (class "Default")
      (node (ref "USB1") (pin "A8") (pinfunction "SBU1_A8") (pintype "passive"))
    )
    (net (code "123") (name "unconnected-(USB1-SBU2-PadB8)") (class "Default")
      (node (ref "USB1") (pin "B8") (pinfunction "SBU2_B8") (pintype "passive"))
    )
    (net (code "124") (name "unconnected-(USB1-TX1+-PadA2)") (class "Default")
      (node (ref "USB1") (pin "A2") (pinfunction "TX1+_A2") (pintype "passive"))
    )
    (net (code "125") (name "unconnected-(USB1-TX1--PadA3)") (class "Default")
      (node (ref "USB1") (pin "A3") (pinfunction "TX1-_A3") (pintype "passive"))
    )
    (net (code "126") (name "unconnected-(USB1-TX2+-PadB2)") (class "Default")
      (node (ref "USB1") (pin "B2") (pinfunction "TX2+_B2") (pintype "passive"))
    )
    (net (code "127") (name "unconnected-(USB1-TX2--PadB3)") (class "Default")
      (node (ref "USB1") (pin "B3") (pinfunction "TX2-_B3") (pintype "passive"))
    )
  )
)
